# main.net
KiCad netlist of a schematic drawn in Altium Designer
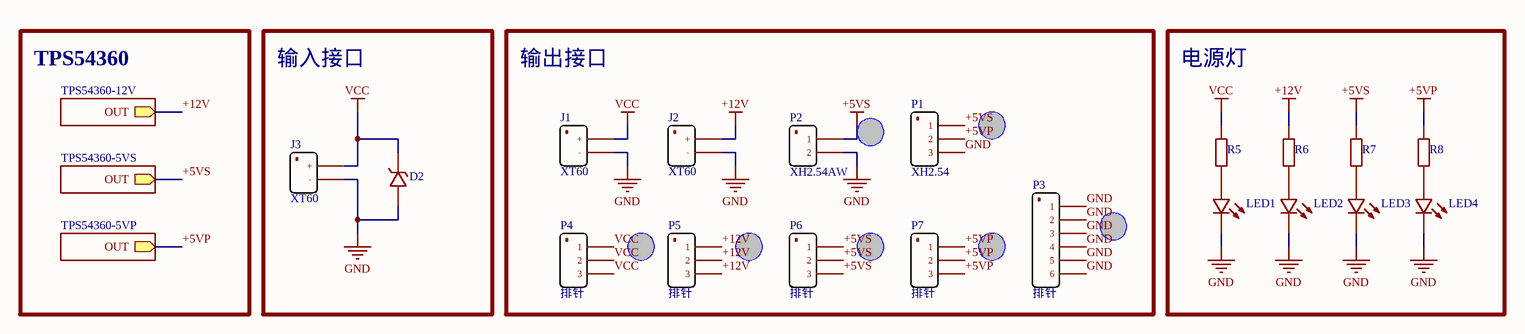
[diagram p0: main.SchDoc]

(export (version "E")
  (design (tool "Eeschema 10.0.6"))
  (components
    (comp (ref "D2") (value "SMAJ24A") (footprint "SMA") (libsource (lib "元件库") (part "二极管_瞬态抑制")))
    (comp (ref "J1") (value "XT60") (footprint "XT30-PW-F") (libsource (lib "接口库") (part "接口_XT")))
    (comp (ref "J2") (value "XT60") (footprint "XT30-PW-F") (libsource (lib "接口库") (part "接口_XT")))
    (comp (ref "J3") (value "XT60") (footprint "XT60-PT-M") (libsource (lib "接口库") (part "接口_XT")))
    (comp (ref "LED1") (value "LED") (footprint "0603D") (libsource (lib "元件库") (part "二极管_贴片发光")))
    (comp (ref "LED2") (value "LED") (footprint "0603D") (libsource (lib "元件库") (part "二极管_贴片发光")))
    (comp (ref "LED3") (value "LED") (footprint "0603D") (libsource (lib "元件库") (part "二极管_贴片发光")))
    (comp (ref "LED4") (value "LED") (footprint "0603D") (libsource (lib "元件库") (part "二极管_贴片发光")))
    (comp (ref "P1") (value "XH2.54") (footprint "XH2.54_AW_1*3") (libsource (lib "接口库") (part "接插件1*3")))
    (comp (ref "P2") (value "XH2.54AW") (footprint "XH2.54_AW_1*2") (libsource (lib "接口库") (part "接插件1*2")))
    (comp (ref "P3") (value "排针") (footprint "Pin-PB-M-1*6") (libsource (lib "接口库") (part "接插件1*6")))
    (comp (ref "P4") (value "排针") (footprint "Pin-PB-M-1*3") (libsource (lib "接口库") (part "接插件1*3")))
    (comp (ref "P5") (value "排针") (footprint "Pin-PB-M-1*3") (libsource (lib "接口库") (part "接插件1*3")))
    (comp (ref "P6") (value "排针") (footprint "Pin-PB-M-1*3") (libsource (lib "接口库") (part "接插件1*3")))
    (comp (ref "P7") (value "排针") (footprint "Pin-PB-M-1*3") (libsource (lib "接口库") (part "接插件1*3")))
    (comp (ref "R5") (value "10K") (footprint "0603R") (libsource (lib "元件库") (part "电阻_贴片")))
    (comp (ref "R6") (value "10K") (footprint "0603R") (libsource (lib "元件库") (part "电阻_贴片")))
    (comp (ref "R7") (value "10K") (footprint "0603R") (libsource (lib "元件库") (part "电阻_贴片")))
    (comp (ref "R8") (value "10K") (footprint "0603R") (libsource (lib "元件库") (part "电阻_贴片")))
  )
  (nets
    (net (code "1") (name "+5VP") (class "Default")
      (node (ref "P1") (pin "2") (pinfunction "2_2") (pintype "passive"))
      (node (ref "P7") (pin "1") (pinfunction "1_1") (pintype "passive"))
      (node (ref "P7") (pin "2") (pinfunction "2_2") (pintype "passive"))
      (node (ref "P7") (pin "3") (pinfunction "3_3") (pintype "passive"))
      (node (ref "R8") (pin "2") (pinfunction "2_2") (pintype "passive"))
    )
    (net (code "2") (name "+5VS") (class "Default")
      (node (ref "P1") (pin "1") (pinfunction "1_1") (pintype "passive"))
      (node (ref "P2") (pin "1") (pinfunction "1_1") (pintype "passive"))
      (node (ref "P6") (pin "1") (pinfunction "1_1") (pintype "passive"))
      (node (ref "P6") (pin "2") (pinfunction "2_2") (pintype "passive"))
      (node (ref "P6") (pin "3") (pinfunction "3_3") (pintype "passive"))
      (node (ref "R7") (pin "2") (pinfunction "2_2") (pintype "passive"))
    )
    (net (code "3") (name "+12V") (class "Default")
      (node (ref "J2") (pin "1") (pinfunction "1_1") (pintype "passive"))
      (node (ref "P5") (pin "1") (pinfunction "1_1") (pintype "passive"))
      (node (ref "P5") (pin "2") (pinfunction "2_2") (pintype "passive"))
      (node (ref "P5") (pin "3") (pinfunction "3_3") (pintype "passive"))
      (node (ref "R6") (pin "2") (pinfunction "2_2") (pintype "passive"))
    )
    (net (code "4") (name "GND") (class "Default")
      (node (ref "D2") (pin "1") (pinfunction "1_1") (pintype "passive"))
      (node (ref "J1") (pin "2") (pinfunction "2_2") (pintype "passive"))
      (node (ref "J2") (pin "2") (pinfunction "2_2") (pintype "passive"))
      (node (ref "J3") (pin "2") (pinfunction "2_2") (pintype "passive"))
      (node (ref "LED1") (pin "2") (pinfunction "2_2") (pintype "passive"))
      (node (ref "LED2") (pin "2") (pinfunction "2_2") (pintype "passive"))
      (node (ref "LED3") (pin "2") (pinfunction "2_2") (pintype "passive"))
      (node (ref "LED4") (pin "2") (pinfunction "2_2") (pintype "passive"))
      (node (ref "P1") (pin "3") (pinfunction "3_3") (pintype "passive"))
      (node (ref "P2") (pin "2") (pinfunction "2_2") (pintype "passive"))
      (node (ref "P3") (pin "1") (pinfunction "1_1") (pintype "passive"))
      (node (ref "P3") (pin "2") (pinfunction "2_2") (pintype "passive"))
      (node (ref "P3") (pin "3") (pinfunction "3_3") (pintype "passive"))
      (node (ref "P3") (pin "4") (pinfunction "4_4") (pintype "passive"))
      (node (ref "P3") (pin "5") (pinfunction "5_5") (pintype "passive"))
      (node (ref "P3") (pin "6") (pinfunction "6_6") (pintype "passive"))
    )
    (net (code "5") (name "Net-(LED1-Pad1)") (class "Default")
      (node (ref "LED1") (pin "1") (pinfunction "1_1") (pintype "passive"))
      (node (ref "R5") (pin "1") (pinfunction "1_1") (pintype "passive"))
    )
    (net (code "6") (name "Net-(LED2-Pad1)") (class "Default")
      (node (ref "LED2") (pin "1") (pinfunction "1_1") (pintype "passive"))
      (node (ref "R6") (pin "1") (pinfunction "1_1") (pintype "passive"))
    )
    (net (code "7") (name "Net-(LED3-Pad1)") (class "Default")
      (node (ref "LED3") (pin "1") (pinfunction "1_1") (pintype "passive"))
      (node (ref "R7") (pin "1") (pinfunction "1_1") (pintype "passive"))
    )
    (net (code "8") (name "Net-(LED4-Pad1)") (class "Default")
      (node (ref "LED4") (pin "1") (pinfunction "1_1") (pintype "passive"))
      (node (ref "R8") (pin "1") (pinfunction "1_1") (pintype "passive"))
    )
    (net (code "9") (name "VCC") (class "Default")
      (node (ref "D2") (pin "2") (pinfunction "2_2") (pintype "passive"))
      (node (ref "J1") (pin "1") (pinfunction "1_1") (pintype "passive"))
      (node (ref "J3") (pin "1") (pinfunction "1_1") (pintype "passive"))
      (node (ref "P4") (pin "1") (pinfunction "1_1") (pintype "passive"))
      (node (ref "P4") (pin "2") (pinfunction "2_2") (pintype "passive"))
      (node (ref "P4") (pin "3") (pinfunction "3_3") (pintype "passive"))
      (node (ref "R5") (pin "2") (pinfunction "2_2") (pintype "passive"))
    )
  )
)
